# 1-HomeSwitch.net
KiCad netlist of a schematic drawn in EAGLE
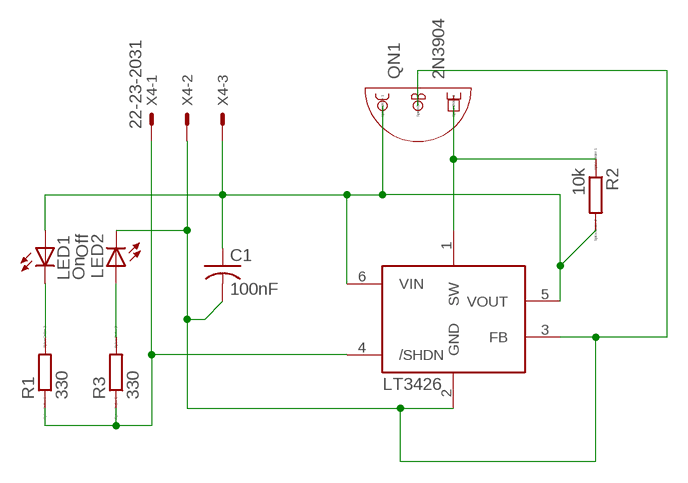
[diagram p0: schematic, sheet 1]

(export (version "E")
  (design (tool "Eeschema 10.0.6"))
  (components
    (comp (ref "C1")
      (value "100nF")
      (footprint "eagle-import:C1210")
      (libsource (lib "eagle-import") (part "C-USC1210"))
    )
    (comp (ref "IC1")
      (value "74LVG1G58GV")
      (footprint "eagle-import:SOT23-6")
      (libsource (lib "eagle-import") (part "LT3426"))
    )
    (comp (ref "LED1")
      (value "On")
      (footprint "eagle-import:LED5MM")
      (libsource (lib "eagle-import") (part "LED5MM"))
    )
    (comp (ref "LED2")
      (value "Off")
      (footprint "eagle-import:LED5MM")
      (libsource (lib "eagle-import") (part "LED5MM"))
    )
    (comp (ref "QN1")
      (value "2N3904")
      (footprint "eagle-import:TO92")
      (libsource (lib "eagle-import") (part "2N3904"))
    )
    (comp (ref "R1")
      (value "330")
      (footprint "eagle-import:R0805")
      (libsource (lib "eagle-import") (part "R"))
    )
    (comp (ref "R2")
      (value "10k")
      (footprint "eagle-import:R0805")
      (libsource (lib "eagle-import") (part "R"))
    )
    (comp (ref "R3")
      (value "330")
      (footprint "eagle-import:R0805")
      (libsource (lib "eagle-import") (part "R"))
    )
    (comp (ref "X4")
      (value "22-23-2031")
      (footprint "eagle-import:22-23-2031")
      (fields (field (name "MF") "MOLEX"))
      (libsource (lib "eagle-import") (part "22-23-2031"))
    )
  )
  (nets
    (net (code "1") (name "Net-(IC1-FB)") (class "Default")
      (node (ref "C1") (pin "2") (pinfunction "2_2") (pintype "passive"))
      (node (ref "IC1") (pin "2") (pinfunction "GND_2") (pintype "power_in"))
      (node (ref "IC1") (pin "3") (pinfunction "FB_3") (pintype "input"))
      (node (ref "LED2") (pin "K") (pinfunction "C_K") (pintype "passive"))
      (node (ref "QN1") (pin "2") (pinfunction "B_2") (pintype "passive"))
      (node (ref "X4") (pin "2") (pinfunction "S_2") (pintype "passive"))
    )
    (net (code "2") (name "Net-(IC1-SW)") (class "Default")
      (node (ref "IC1") (pin "1") (pinfunction "SW_1") (pintype "output"))
      (node (ref "QN1") (pin "3") (pinfunction "E_3") (pintype "passive"))
      (node (ref "R2") (pin "1") (pinfunction "1_1") (pintype "passive"))
    )
    (net (code "3") (name "Net-(IC1-VIN)") (class "Default")
      (node (ref "C1") (pin "1") (pinfunction "1_1") (pintype "passive"))
      (node (ref "IC1") (pin "5") (pinfunction "VOUT_5") (pintype "output"))
      (node (ref "IC1") (pin "6") (pinfunction "VIN_6") (pintype "input"))
      (node (ref "LED1") (pin "A") (pinfunction "A_A") (pintype "passive"))
      (node (ref "QN1") (pin "1") (pinfunction "C_1") (pintype "passive"))
      (node (ref "R2") (pin "2") (pinfunction "2_2") (pintype "passive"))
      (node (ref "X4") (pin "3") (pinfunction "S_3") (pintype "passive"))
    )
    (net (code "4") (name "Net-(IC1-{slash}SHDN)") (class "Default")
      (node (ref "IC1") (pin "4") (pinfunction "/SHDN_4") (pintype "input"))
      (node (ref "R1") (pin "1") (pinfunction "1_1") (pintype "passive"))
      (node (ref "R3") (pin "1") (pinfunction "1_1") (pintype "passive"))
      (node (ref "X4") (pin "1") (pinfunction "S_1") (pintype "passive"))
    )
    (net (code "5") (name "Net-(LED1-C)") (class "Default")
      (node (ref "LED1") (pin "K") (pinfunction "C_K") (pintype "passive"))
      (node (ref "R1") (pin "2") (pinfunction "2_2") (pintype "passive"))
    )
    (net (code "6") (name "Net-(LED2-PadA)") (class "Default")
      (node (ref "LED2") (pin "A") (pinfunction "A_A") (pintype "passive"))
      (node (ref "R3") (pin "2") (pinfunction "2_2") (pintype "passive"))
    )
  )
)
